# USB_Input.net
KiCad netlist of a schematic drawn in Altium Designer
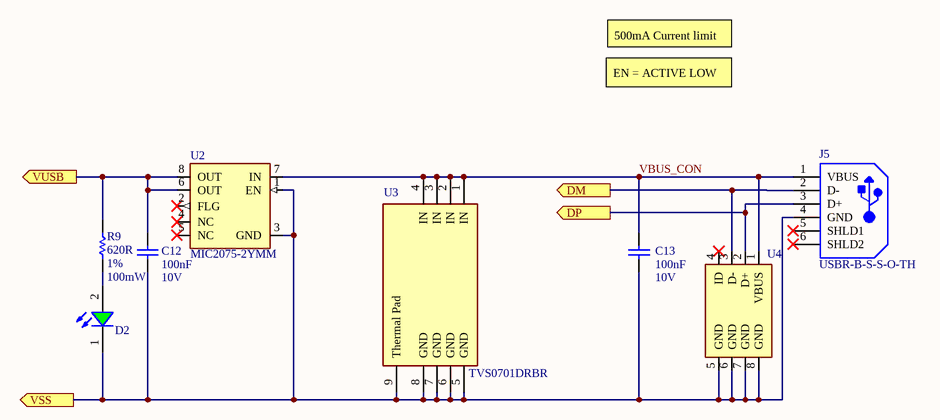
[diagram p0: USB Input.SchDoc]

(export (version "E")
  (design (tool "Eeschema 10.0.6"))
  (components
    (comp (ref "C12")
      (value "C0402C104K8PACTU")
      (footprint "0402 CAPACITOR")
      (description "Cap Ceramic 0.1uF 10V X5R 10% SMD 0402 85°C")
      (fields
        (field (name "CAPACITANCE") "100nF")
        (field (name "VOLTAGE RATING") "10V")
        (field (name "VOLTAGE") "10V")
        (field (name "TOLERANCE") "10%")
      )
      (libsource (lib "Premier EDA Student Advantage Programme") (part "Capacitor"))
    )
    (comp (ref "C13")
      (value "C0402C104K8PACTU")
      (footprint "0402 CAPACITOR")
      (description "Cap Ceramic 0.1uF 10V X5R 10% SMD 0402 85°C")
      (fields
        (field (name "CAPACITANCE") "100nF")
        (field (name "VOLTAGE RATING") "10V")
        (field (name "VOLTAGE") "10V")
        (field (name "TOLERANCE") "10%")
      )
      (libsource (lib "Premier EDA Student Advantage Programme") (part "Capacitor"))
    )
    (comp (ref "D2")
      (value "150060VS73220")
      (footprint "WL-SMCC_0603_RS_VS_YS")
      (description "WL-SMCC SMD Mono-color Chip LED Compact, size 0603, Bright Green, 2V, 120deg")
      (fields (field (name "PUBLISHER") "Wurth Elektronik"))
      (libsource (lib "Altium_WL-SMCC_rev19a") (part "150060VS73220"))
    )
    (comp (ref "J5")
      (value "USBR-B-S-S-O-TH")
      (footprint "SMTC-USBR-TH-4_V")
      (description "Conn USB F 4 POS 2.5mm Solder RA Thru-Hole 4 Terminal 1 Port Tray")
      (fields (field (name "MANUFACTURER") "SamtecInc."))
      (libsource (lib "Premier EDA Student Advantage Programme") (part "CMP-2000-07371-1"))
    )
    (comp (ref "R9")
      (value "MCMR06X6200FTL")
      (footprint "0603 RESISTOR")
      (description "RES, CERAMIC, 620R, 1%, 0.1W, 0603")
      (fields
        (field (name "RESISTANCE") "620R")
        (field (name "TOLERANCE") "1%")
        (field (name "POWER RATING") "100mW")
      )
      (libsource (lib "Premier EDA Student Advantage Programme") (part "Resistor"))
    )
    (comp (ref "U2")
      (value "MIC2075-2YMM")
      (footprint "TSOP65P490X102-8N")
      (description "MIC2075 Series 5.5 V 140 mOhm Single-Channel Power Distribution Switch - SOIC-8")
      (libsource (lib "Premier EDA Student Advantage Programme") (part "MIC2075-2YMM"))
    )
    (comp (ref "U3")
      (value "TVS0701DRBR")
      (footprint "FP-DRB0008A-MFG")
      (description "TVS ARRAYS")
      (fields
        (field (name "MANUFACTURER") "Texas instruments")
        (field (name "OCTOPART") "https://octopart.com/tvs0701drbr-texas+instruments-96189204")
      )
      (libsource (lib "Altium Content Vault") (part "677dffaeec8be7f37c72b3775095c82"))
    )
    (comp (ref "U4")
      (value "Rclamp1255P.TGT")
      (footprint "SON40P200X65-8N")
      (description "Tvs Diode 4V 12.5V SLP2018P6")
      (libsource (lib "Premier EDA Student Advantage Programme") (part "Rclamp1255P.TGT"))
    )
  )
  (nets
    (net (code "1") (name "/DM") (class "Default")
      (node (ref "J5") (pin "2") (pinfunction "D-_2") (pintype "passive"))
      (node (ref "U4") (pin "3") (pinfunction "D-_3") (pintype "power_in"))
    )
    (net (code "2") (name "/DP") (class "Default")
      (node (ref "J5") (pin "3") (pinfunction "D+_3") (pintype "passive"))
      (node (ref "U4") (pin "2") (pinfunction "D+_2") (pintype "power_in"))
    )
    (net (code "3") (name "/VBUS_CON") (class "Default")
      (node (ref "C13") (pin "2") (pinfunction "2_2") (pintype "power_in"))
      (node (ref "J5") (pin "1") (pinfunction "VBUS_1") (pintype "passive"))
      (node (ref "U2") (pin "7") (pinfunction "IN_7") (pintype "power_in"))
      (node (ref "U3") (pin "1") (pinfunction "IN_1") (pintype "passive"))
      (node (ref "U3") (pin "2") (pinfunction "IN_2") (pintype "passive"))
      (node (ref "U3") (pin "3") (pinfunction "IN_3") (pintype "passive"))
      (node (ref "U3") (pin "4") (pinfunction "IN_4") (pintype "passive"))
      (node (ref "U4") (pin "1") (pinfunction "VBUS_1") (pintype "power_in"))
    )
    (net (code "4") (name "/VSS") (class "Default")
      (node (ref "C12") (pin "1") (pinfunction "1_1") (pintype "power_in"))
      (node (ref "C13") (pin "1") (pinfunction "1_1") (pintype "power_in"))
      (node (ref "D2") (pin "1") (pinfunction "K_1") (pintype "passive"))
      (node (ref "J5") (pin "4") (pinfunction "GND_4") (pintype "passive"))
      (node (ref "U2") (pin "1") (pinfunction "EN_1") (pintype "input"))
      (node (ref "U2") (pin "3") (pinfunction "GND_3") (pintype "power_in"))
      (node (ref "U3") (pin "5") (pinfunction "GND_5") (pintype "power_in"))
      (node (ref "U3") (pin "6") (pinfunction "GND_6") (pintype "power_in"))
      (node (ref "U3") (pin "7") (pinfunction "GND_7") (pintype "power_in"))
      (node (ref "U3") (pin "8") (pinfunction "GND_8") (pintype "power_in"))
      (node (ref "U3") (pin "9") (pinfunction "Thermal_Pad_9") (pintype "passive"))
      (node (ref "U4") (pin "5") (pinfunction "GND_5") (pintype "power_in"))
      (node (ref "U4") (pin "6") (pinfunction "GND_6") (pintype "power_in"))
      (node (ref "U4") (pin "7") (pinfunction "GND_7") (pintype "power_in"))
      (node (ref "U4") (pin "8") (pinfunction "GND_8") (pintype "power_in"))
    )
    (net (code "5") (name "/VUSB") (class "Default")
      (node (ref "C12") (pin "2") (pinfunction "2_2") (pintype "power_in"))
      (node (ref "R9") (pin "2") (pinfunction "2_2") (pintype "power_in"))
      (node (ref "U2") (pin "6") (pinfunction "OUT_6") (pintype "power_in"))
      (node (ref "U2") (pin "8") (pinfunction "OUT_8") (pintype "power_in"))
    )
    (net (code "6") (name "Net-(D2-A)") (class "Default")
      (node (ref "D2") (pin "2") (pinfunction "A_2") (pintype "passive"))
      (node (ref "R9") (pin "1") (pinfunction "1_1") (pintype "power_in"))
    )
    (net (code "7") (name "unconnected-(J5-SHLD1-Pad5)") (class "Default")
      (node (ref "J5") (pin "5") (pinfunction "SHLD1_5") (pintype "passive+no_connect"))
    )
    (net (code "8") (name "unconnected-(J5-SHLD2-Pad6)") (class "Default")
      (node (ref "J5") (pin "6") (pinfunction "SHLD2_6") (pintype "passive+no_connect"))
    )
    (net (code "9") (name "unconnected-(U2-FLG-Pad2)") (class "Default")
      (node (ref "U2") (pin "2") (pinfunction "FLG_2") (pintype "output+no_connect"))
    )
    (net (code "10") (name "unconnected-(U2-NC-Pad4)") (class "Default")
      (node (ref "U2") (pin "4") (pinfunction "NC_4") (pintype "passive+no_connect"))
    )
    (net (code "11") (name "unconnected-(U2-NC-Pad5)") (class "Default")
      (node (ref "U2") (pin "5") (pinfunction "NC_5") (pintype "passive+no_connect"))
    )
    (net (code "12") (name "unconnected-(U4-ID-Pad4)") (class "Default")
      (node (ref "U4") (pin "4") (pinfunction "ID_4") (pintype "power_in+no_connect"))
    )
  )
)
